# Breakout.net
KiCad netlist of a schematic drawn in EAGLE
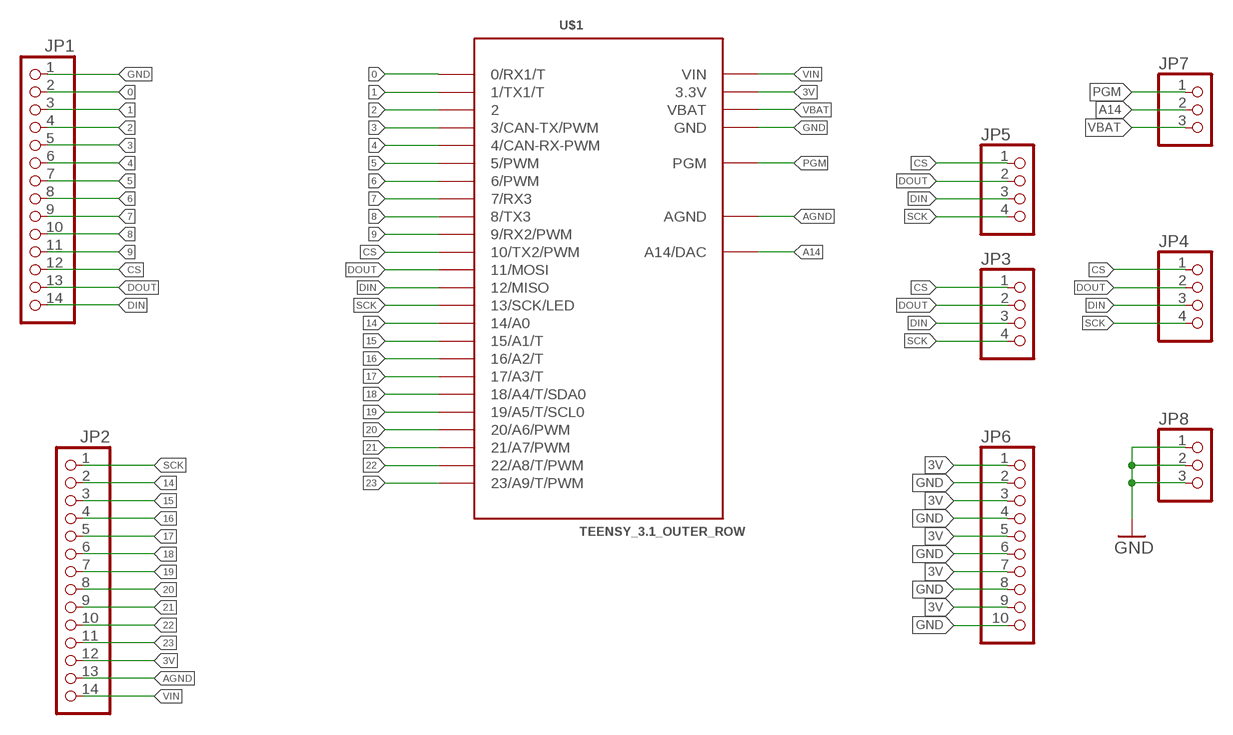
[diagram p0: schematic, sheet 1]

(export (version "E")
  (design (tool "Eeschema 10.0.6"))
  (components
    (comp (ref "JP1")
      (value "PINHD-1X14")
      (footprint "eagle-import:1X14")
      (libsource (lib "eagle-import") (part "PINHD-1X14"))
    )
    (comp (ref "JP2")
      (value "PINHD-1X14")
      (footprint "eagle-import:1X14")
      (libsource (lib "eagle-import") (part "PINHD-1X14"))
    )
    (comp (ref "JP3")
      (value "PINHD-1X4")
      (footprint "eagle-import:1X04")
      (libsource (lib "eagle-import") (part "PINHD-1X4"))
    )
    (comp (ref "JP4")
      (value "PINHD-1X4")
      (footprint "eagle-import:1X04")
      (libsource (lib "eagle-import") (part "PINHD-1X4"))
    )
    (comp (ref "JP5")
      (value "PINHD-1X4")
      (footprint "eagle-import:1X04")
      (libsource (lib "eagle-import") (part "PINHD-1X4"))
    )
    (comp (ref "JP6")
      (value "PINHD-1X10")
      (footprint "eagle-import:1X10")
      (libsource (lib "eagle-import") (part "PINHD-1X10"))
    )
    (comp (ref "JP7")
      (value "PINHD-1X3")
      (footprint "eagle-import:1X03")
      (libsource (lib "eagle-import") (part "PINHD-1X3"))
    )
    (comp (ref "JP8")
      (value "PINHD-1X3")
      (footprint "eagle-import:1X03")
      (libsource (lib "eagle-import") (part "PINHD-1X3"))
    )
    (comp (ref "U$1")
      (value "TEENSY_3.1_OUTER_ROW")
      (footprint "eagle-import:TEENSY3-OUTER_ROW")
      (libsource (lib "eagle-import") (part "TEENSY_3.1_OUTER_ROW"))
    )
  )
  (nets
    (net (code "1") (name "0") (class "Default")
      (node (ref "JP1") (pin "2") (pinfunction "2_2") (pintype "passive"))
      (node (ref "U$1") (pin "0") (pinfunction "0/RX1/T_0") (pintype "bidirectional"))
    )
    (net (code "2") (name "1") (class "Default")
      (node (ref "JP1") (pin "3") (pinfunction "3_3") (pintype "passive"))
      (node (ref "U$1") (pin "1") (pinfunction "1/TX1/T_1") (pintype "bidirectional"))
    )
    (net (code "3") (name "2") (class "Default")
      (node (ref "JP1") (pin "4") (pinfunction "4_4") (pintype "passive"))
      (node (ref "U$1") (pin "2") (pinfunction "2_2") (pintype "bidirectional"))
    )
    (net (code "4") (name "3") (class "Default")
      (node (ref "JP1") (pin "5") (pinfunction "5_5") (pintype "passive"))
      (node (ref "U$1") (pin "3") (pinfunction "3/CAN-TX/PWM_3") (pintype "bidirectional"))
    )
    (net (code "5") (name "3V") (class "Default")
      (node (ref "JP2") (pin "12") (pinfunction "12_12") (pintype "passive"))
      (node (ref "JP6") (pin "1") (pinfunction "1_1") (pintype "passive"))
      (node (ref "JP6") (pin "3") (pinfunction "3_3") (pintype "passive"))
      (node (ref "JP6") (pin "5") (pinfunction "5_5") (pintype "passive"))
      (node (ref "JP6") (pin "7") (pinfunction "7_7") (pintype "passive"))
      (node (ref "JP6") (pin "9") (pinfunction "9_9") (pintype "passive"))
      (node (ref "U$1") (pin "3.3V") (pinfunction "3.3V_3.3V") (pintype "power_in"))
      (node (ref "U$1") (pin "3.3V1") (pinfunction "3.3V_3.3V1") (pintype "power_in"))
    )
    (net (code "6") (name "4") (class "Default")
      (node (ref "JP1") (pin "6") (pinfunction "6_6") (pintype "passive"))
      (node (ref "U$1") (pin "4") (pinfunction "4/CAN-RX-PWM_4") (pintype "bidirectional"))
    )
    (net (code "7") (name "5") (class "Default")
      (node (ref "JP1") (pin "7") (pinfunction "7_7") (pintype "passive"))
      (node (ref "U$1") (pin "5") (pinfunction "5/PWM_5") (pintype "bidirectional"))
    )
    (net (code "8") (name "6") (class "Default")
      (node (ref "JP1") (pin "8") (pinfunction "8_8") (pintype "passive"))
      (node (ref "U$1") (pin "6") (pinfunction "6/PWM_6") (pintype "bidirectional"))
    )
    (net (code "9") (name "7") (class "Default")
      (node (ref "JP1") (pin "9") (pinfunction "9_9") (pintype "passive"))
      (node (ref "U$1") (pin "7") (pinfunction "7/RX3_7") (pintype "bidirectional"))
    )
    (net (code "10") (name "8") (class "Default")
      (node (ref "JP1") (pin "10") (pinfunction "10_10") (pintype "passive"))
      (node (ref "U$1") (pin "8") (pinfunction "8/TX3_8") (pintype "bidirectional"))
    )
    (net (code "11") (name "9") (class "Default")
      (node (ref "JP1") (pin "11") (pinfunction "11_11") (pintype "passive"))
      (node (ref "U$1") (pin "9") (pinfunction "9/RX2/PWM_9") (pintype "bidirectional"))
    )
    (net (code "12") (name "14") (class "Default")
      (node (ref "JP2") (pin "2") (pinfunction "2_2") (pintype "passive"))
      (node (ref "U$1") (pin "14/A0") (pinfunction "14/A0_14/A0") (pintype "bidirectional"))
    )
    (net (code "13") (name "15") (class "Default")
      (node (ref "JP2") (pin "3") (pinfunction "3_3") (pintype "passive"))
      (node (ref "U$1") (pin "15/A1") (pinfunction "15/A1/T_15/A1") (pintype "bidirectional"))
    )
    (net (code "14") (name "16") (class "Default")
      (node (ref "JP2") (pin "4") (pinfunction "4_4") (pintype "passive"))
      (node (ref "U$1") (pin "16/A2") (pinfunction "16/A2/T_16/A2") (pintype "bidirectional"))
    )
    (net (code "15") (name "17") (class "Default")
      (node (ref "JP2") (pin "5") (pinfunction "5_5") (pintype "passive"))
      (node (ref "U$1") (pin "17/A3") (pinfunction "17/A3/T_17/A3") (pintype "bidirectional"))
    )
    (net (code "16") (name "18") (class "Default")
      (node (ref "JP2") (pin "6") (pinfunction "6_6") (pintype "passive"))
      (node (ref "U$1") (pin "18/A4") (pinfunction "18/A4/T/SDA0_18/A4") (pintype "bidirectional"))
    )
    (net (code "17") (name "19") (class "Default")
      (node (ref "JP2") (pin "7") (pinfunction "7_7") (pintype "passive"))
      (node (ref "U$1") (pin "19/A5") (pinfunction "19/A5/T/SCL0_19/A5") (pintype "bidirectional"))
    )
    (net (code "18") (name "20") (class "Default")
      (node (ref "JP2") (pin "8") (pinfunction "8_8") (pintype "passive"))
      (node (ref "U$1") (pin "20/A6") (pinfunction "20/A6/PWM_20/A6") (pintype "bidirectional"))
    )
    (net (code "19") (name "21") (class "Default")
      (node (ref "JP2") (pin "9") (pinfunction "9_9") (pintype "passive"))
      (node (ref "U$1") (pin "21/A7") (pinfunction "21/A7/PWM_21/A7") (pintype "bidirectional"))
    )
    (net (code "20") (name "22") (class "Default")
      (node (ref "JP2") (pin "10") (pinfunction "10_10") (pintype "passive"))
      (node (ref "U$1") (pin "22/A8") (pinfunction "22/A8/T/PWM_22/A8") (pintype "bidirectional"))
    )
    (net (code "21") (name "23") (class "Default")
      (node (ref "JP2") (pin "11") (pinfunction "11_11") (pintype "passive"))
      (node (ref "U$1") (pin "23/A9") (pinfunction "23/A9/T/PWM_23/A9") (pintype "bidirectional"))
    )
    (net (code "22") (name "A14") (class "Default")
      (node (ref "JP7") (pin "2") (pinfunction "2_2") (pintype "passive"))
      (node (ref "U$1") (pin "RESET/DAC") (pinfunction "A14/DAC_RESET/DAC") (pintype "bidirectional"))
    )
    (net (code "23") (name "AGND") (class "Default")
      (node (ref "JP2") (pin "13") (pinfunction "13_13") (pintype "passive"))
      (node (ref "U$1") (pin "AGND") (pinfunction "AGND_AGND") (pintype "power_in"))
    )
    (net (code "24") (name "CS") (class "Default")
      (node (ref "JP1") (pin "12") (pinfunction "12_12") (pintype "passive"))
      (node (ref "JP3") (pin "1") (pinfunction "1_1") (pintype "passive"))
      (node (ref "JP4") (pin "1") (pinfunction "1_1") (pintype "passive"))
      (node (ref "JP5") (pin "1") (pinfunction "1_1") (pintype "passive"))
      (node (ref "U$1") (pin "10") (pinfunction "10/TX2/PWM_10") (pintype "bidirectional"))
    )
    (net (code "25") (name "DIN") (class "Default")
      (node (ref "JP1") (pin "14") (pinfunction "14_14") (pintype "passive"))
      (node (ref "JP3") (pin "3") (pinfunction "3_3") (pintype "passive"))
      (node (ref "JP4") (pin "3") (pinfunction "3_3") (pintype "passive"))
      (node (ref "JP5") (pin "3") (pinfunction "3_3") (pintype "passive"))
      (node (ref "U$1") (pin "12") (pinfunction "12/MISO_12") (pintype "bidirectional"))
    )
    (net (code "26") (name "DOUT") (class "Default")
      (node (ref "JP1") (pin "13") (pinfunction "13_13") (pintype "passive"))
      (node (ref "JP3") (pin "2") (pinfunction "2_2") (pintype "passive"))
      (node (ref "JP4") (pin "2") (pinfunction "2_2") (pintype "passive"))
      (node (ref "JP5") (pin "2") (pinfunction "2_2") (pintype "passive"))
      (node (ref "U$1") (pin "11") (pinfunction "11/MOSI_11") (pintype "bidirectional"))
    )
    (net (code "27") (name "GND") (class "Default")
      (node (ref "JP1") (pin "1") (pinfunction "1_1") (pintype "passive"))
      (node (ref "JP6") (pin "10") (pinfunction "10_10") (pintype "passive"))
      (node (ref "JP6") (pin "2") (pinfunction "2_2") (pintype "passive"))
      (node (ref "JP6") (pin "4") (pinfunction "4_4") (pintype "passive"))
      (node (ref "JP6") (pin "6") (pinfunction "6_6") (pintype "passive"))
      (node (ref "JP6") (pin "8") (pinfunction "8_8") (pintype "passive"))
      (node (ref "JP8") (pin "1") (pinfunction "1_1") (pintype "passive"))
      (node (ref "JP8") (pin "2") (pinfunction "2_2") (pintype "passive"))
      (node (ref "JP8") (pin "3") (pinfunction "3_3") (pintype "passive"))
      (node (ref "U$1") (pin "GND") (pinfunction "GND_GND") (pintype "power_in"))
      (node (ref "U$1") (pin "GND1") (pinfunction "GND_GND1") (pintype "power_in"))
    )
    (net (code "28") (name "PGM") (class "Default")
      (node (ref "JP7") (pin "1") (pinfunction "1_1") (pintype "passive"))
      (node (ref "U$1") (pin "PGM") (pinfunction "PGM_PGM") (pintype "bidirectional"))
    )
    (net (code "29") (name "SCK") (class "Default")
      (node (ref "JP2") (pin "1") (pinfunction "1_1") (pintype "passive"))
      (node (ref "JP3") (pin "4") (pinfunction "4_4") (pintype "passive"))
      (node (ref "JP4") (pin "4") (pinfunction "4_4") (pintype "passive"))
      (node (ref "JP5") (pin "4") (pinfunction "4_4") (pintype "passive"))
      (node (ref "U$1") (pin "13") (pinfunction "13/SCK/LED_13") (pintype "bidirectional"))
    )
    (net (code "30") (name "VBAT") (class "Default")
      (node (ref "JP7") (pin "3") (pinfunction "3_3") (pintype "passive"))
      (node (ref "U$1") (pin "VBAT") (pinfunction "VBAT_VBAT") (pintype "power_in"))
    )
    (net (code "31") (name "VIN") (class "Default")
      (node (ref "JP2") (pin "14") (pinfunction "14_14") (pintype "passive"))
      (node (ref "U$1") (pin "VIN") (pinfunction "VIN_VIN") (pintype "power_in"))
    )
  )
)
